# I2C_Switch.net
KiCad netlist of a schematic drawn in Altium Designer
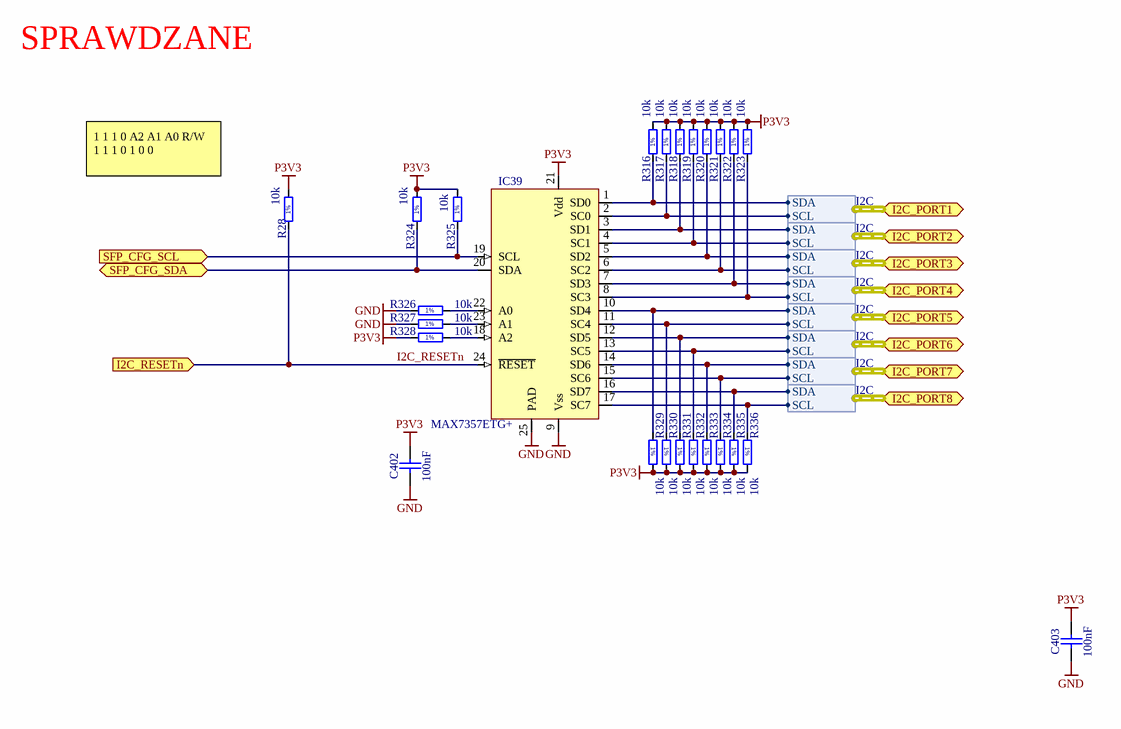
[diagram p0: I2C_Switch.SchDoc]

(export (version "E")
  (design (tool "Eeschema 10.0.6"))
  (components
    (comp (ref "C402")
      (value "100nF")
      (footprint "CAPC0603X33N")
      (description "Non-polarised capacitor")
      (fields
        (field (name "PART NUMBER") "CC0201_100NF_6.3V_10%_X5R")
        (field (name "VOLTAGE") "6.3V")
        (field (name "AUTHOR") "CERN DEM JLC")
      )
      (libsource (lib "Capacitors") (part "Capacitor - non polarized"))
    )
    (comp (ref "C403")
      (value "100nF")
      (footprint "CAPC0603X33N")
      (description "Non-polarised capacitor")
      (fields
        (field (name "PART NUMBER") "CC0201_100NF_6.3V_10%_X5R")
        (field (name "VOLTAGE") "6.3V")
        (field (name "AUTHOR") "CERN DEM JLC")
      )
      (libsource (lib "Capacitors") (part "Capacitor - non polarized"))
    )
    (comp (ref "IC39")
      (value "MAX7357ETG+")
      (footprint "QFN50P400X400X80-25N-S265")
      (description "8-channel I2C-bus multiplexer with reset, INT and timeout")
      (fields (field (name "MANUFACTURER") "MAXIM") (field (name "AUTHOR") "LNLS DIG GBMB"))
      (libsource (lib "ICs And Semiconductors") (part "MAX7357"))
    )
    (comp (ref "R28")
      (value "10k")
      (footprint "RESC1005X40N")
      (description "Resistor - 1%")
      (fields
        (field (name "PART NUMBER") "R0402_10K_1%_0.0625W_100PPM")
        (field (name "POWER") "0.0625W")
        (field (name "AUTHOR") "CERN DEM JLC")
      )
      (libsource (lib "Resistors") (part "Resistor - 1%"))
    )
    (comp (ref "R316")
      (value "10k")
      (footprint "RESC1005X40N")
      (description "Resistor - 1%")
      (fields
        (field (name "PART NUMBER") "R0402_10K_1%_0.0625W_100PPM")
        (field (name "POWER") "0.0625W")
        (field (name "AUTHOR") "CERN DEM JLC")
      )
      (libsource (lib "Resistors") (part "Resistor - 1%"))
    )
    (comp (ref "R317")
      (value "10k")
      (footprint "RESC1005X40N")
      (description "Resistor - 1%")
      (fields
        (field (name "PART NUMBER") "R0402_10K_1%_0.0625W_100PPM")
        (field (name "POWER") "0.0625W")
        (field (name "AUTHOR") "CERN DEM JLC")
      )
      (libsource (lib "Resistors") (part "Resistor - 1%"))
    )
    (comp (ref "R318")
      (value "10k")
      (footprint "RESC1005X40N")
      (description "Resistor - 1%")
      (fields
        (field (name "PART NUMBER") "R0402_10K_1%_0.0625W_100PPM")
        (field (name "POWER") "0.0625W")
        (field (name "AUTHOR") "CERN DEM JLC")
      )
      (libsource (lib "Resistors") (part "Resistor - 1%"))
    )
    (comp (ref "R319")
      (value "10k")
      (footprint "RESC1005X40N")
      (description "Resistor - 1%")
      (fields
        (field (name "PART NUMBER") "R0402_10K_1%_0.0625W_100PPM")
        (field (name "POWER") "0.0625W")
        (field (name "AUTHOR") "CERN DEM JLC")
      )
      (libsource (lib "Resistors") (part "Resistor - 1%"))
    )
    (comp (ref "R320")
      (value "10k")
      (footprint "RESC1005X40N")
      (description "Resistor - 1%")
      (fields
        (field (name "PART NUMBER") "R0402_10K_1%_0.0625W_100PPM")
        (field (name "POWER") "0.0625W")
        (field (name "AUTHOR") "CERN DEM JLC")
      )
      (libsource (lib "Resistors") (part "Resistor - 1%"))
    )
    (comp (ref "R321")
      (value "10k")
      (footprint "RESC1005X40N")
      (description "Resistor - 1%")
      (fields
        (field (name "PART NUMBER") "R0402_10K_1%_0.0625W_100PPM")
        (field (name "POWER") "0.0625W")
        (field (name "AUTHOR") "CERN DEM JLC")
      )
      (libsource (lib "Resistors") (part "Resistor - 1%"))
    )
    (comp (ref "R322")
      (value "10k")
      (footprint "RESC1005X40N")
      (description "Resistor - 1%")
      (fields
        (field (name "PART NUMBER") "R0402_10K_1%_0.0625W_100PPM")
        (field (name "POWER") "0.0625W")
        (field (name "AUTHOR") "CERN DEM JLC")
      )
      (libsource (lib "Resistors") (part "Resistor - 1%"))
    )
    (comp (ref "R323")
      (value "10k")
      (footprint "RESC1005X40N")
      (description "Resistor - 1%")
      (fields
        (field (name "PART NUMBER") "R0402_10K_1%_0.0625W_100PPM")
        (field (name "POWER") "0.0625W")
        (field (name "AUTHOR") "CERN DEM JLC")
      )
      (libsource (lib "Resistors") (part "Resistor - 1%"))
    )
    (comp (ref "R324")
      (value "10k")
      (footprint "RESC1005X40N")
      (description "Resistor - 1%")
      (fields
        (field (name "PART NUMBER") "R0402_10K_1%_0.0625W_100PPM")
        (field (name "POWER") "0.0625W")
        (field (name "AUTHOR") "CERN DEM JLC")
      )
      (libsource (lib "Resistors") (part "Resistor - 1%"))
    )
    (comp (ref "R325")
      (value "10k")
      (footprint "RESC1005X40N")
      (description "Resistor - 1%")
      (fields
        (field (name "PART NUMBER") "R0402_10K_1%_0.0625W_100PPM")
        (field (name "POWER") "0.0625W")
        (field (name "AUTHOR") "CERN DEM JLC")
      )
      (libsource (lib "Resistors") (part "Resistor - 1%"))
    )
    (comp (ref "R326")
      (value "10k")
      (footprint "RESC1005X40N")
      (description "Resistor - 1%")
      (fields
        (field (name "PART NUMBER") "R0402_10K_1%_0.0625W_100PPM")
        (field (name "POWER") "0.0625W")
        (field (name "AUTHOR") "CERN DEM JLC")
      )
      (libsource (lib "Resistors") (part "Resistor - 1%"))
    )
    (comp (ref "R327")
      (value "10k")
      (footprint "RESC1005X40N")
      (description "Resistor - 1%")
      (fields
        (field (name "PART NUMBER") "R0402_10K_1%_0.0625W_100PPM")
        (field (name "POWER") "0.0625W")
        (field (name "AUTHOR") "CERN DEM JLC")
      )
      (libsource (lib "Resistors") (part "Resistor - 1%"))
    )
    (comp (ref "R328")
      (value "10k")
      (footprint "RESC1005X40N")
      (description "Resistor - 1%")
      (fields
        (field (name "PART NUMBER") "R0402_10K_1%_0.0625W_100PPM")
        (field (name "POWER") "0.0625W")
        (field (name "AUTHOR") "CERN DEM JLC")
      )
      (libsource (lib "Resistors") (part "Resistor - 1%"))
    )
    (comp (ref "R329")
      (value "10k")
      (footprint "RESC1005X40N")
      (description "Resistor - 1%")
      (fields
        (field (name "PART NUMBER") "R0402_10K_1%_0.0625W_100PPM")
        (field (name "POWER") "0.0625W")
        (field (name "AUTHOR") "CERN DEM JLC")
      )
      (libsource (lib "Resistors") (part "Resistor - 1%"))
    )
    (comp (ref "R330")
      (value "10k")
      (footprint "RESC1005X40N")
      (description "Resistor - 1%")
      (fields
        (field (name "PART NUMBER") "R0402_10K_1%_0.0625W_100PPM")
        (field (name "POWER") "0.0625W")
        (field (name "AUTHOR") "CERN DEM JLC")
      )
      (libsource (lib "Resistors") (part "Resistor - 1%"))
    )
    (comp (ref "R331")
      (value "10k")
      (footprint "RESC1005X40N")
      (description "Resistor - 1%")
      (fields
        (field (name "PART NUMBER") "R0402_10K_1%_0.0625W_100PPM")
        (field (name "POWER") "0.0625W")
        (field (name "AUTHOR") "CERN DEM JLC")
      )
      (libsource (lib "Resistors") (part "Resistor - 1%"))
    )
    (comp (ref "R332")
      (value "10k")
      (footprint "RESC1005X40N")
      (description "Resistor - 1%")
      (fields
        (field (name "PART NUMBER") "R0402_10K_1%_0.0625W_100PPM")
        (field (name "POWER") "0.0625W")
        (field (name "AUTHOR") "CERN DEM JLC")
      )
      (libsource (lib "Resistors") (part "Resistor - 1%"))
    )
    (comp (ref "R333")
      (value "10k")
      (footprint "RESC1005X40N")
      (description "Resistor - 1%")
      (fields
        (field (name "PART NUMBER") "R0402_10K_1%_0.0625W_100PPM")
        (field (name "POWER") "0.0625W")
        (field (name "AUTHOR") "CERN DEM JLC")
      )
      (libsource (lib "Resistors") (part "Resistor - 1%"))
    )
    (comp (ref "R334")
      (value "10k")
      (footprint "RESC1005X40N")
      (description "Resistor - 1%")
      (fields
        (field (name "PART NUMBER") "R0402_10K_1%_0.0625W_100PPM")
        (field (name "POWER") "0.0625W")
        (field (name "AUTHOR") "CERN DEM JLC")
      )
      (libsource (lib "Resistors") (part "Resistor - 1%"))
    )
    (comp (ref "R335")
      (value "10k")
      (footprint "RESC1005X40N")
      (description "Resistor - 1%")
      (fields
        (field (name "PART NUMBER") "R0402_10K_1%_0.0625W_100PPM")
        (field (name "POWER") "0.0625W")
        (field (name "AUTHOR") "CERN DEM JLC")
      )
      (libsource (lib "Resistors") (part "Resistor - 1%"))
    )
    (comp (ref "R336")
      (value "10k")
      (footprint "RESC1005X40N")
      (description "Resistor - 1%")
      (fields
        (field (name "PART NUMBER") "R0402_10K_1%_0.0625W_100PPM")
        (field (name "POWER") "0.0625W")
        (field (name "AUTHOR") "CERN DEM JLC")
      )
      (libsource (lib "Resistors") (part "Resistor - 1%"))
    )
  )
  (nets
    (net (code "4") (name "/I2C_RESETn") (class "Default")
      (node (ref "IC39") (pin "24") (pinfunction "~{RESET}_24") (pintype "input"))
      (node (ref "R28") (pin "1") (pinfunction "1_1") (pintype "passive"))
    )
    (net (code "5") (name "/SFP_CFG_SCL") (class "Default")
      (node (ref "IC39") (pin "19") (pinfunction "SCL_19") (pintype "input"))
      (node (ref "R325") (pin "1") (pinfunction "1_1") (pintype "passive"))
    )
    (net (code "6") (name "/SFP_CFG_SDA") (class "Default")
      (node (ref "IC39") (pin "20") (pinfunction "SDA_20") (pintype "bidirectional"))
      (node (ref "R324") (pin "1") (pinfunction "1_1") (pintype "passive"))
    )
    (net (code "8") (name "GND") (class "Default")
      (node (ref "C402") (pin "1") (pinfunction "1_1") (pintype "passive"))
      (node (ref "C403") (pin "1") (pinfunction "1_1") (pintype "passive"))
      (node (ref "IC39") (pin "25") (pinfunction "PAD_25") (pintype "power_in"))
      (node (ref "IC39") (pin "9") (pinfunction "Vss_9") (pintype "power_in"))
      (node (ref "R326") (pin "1") (pinfunction "1_1") (pintype "passive"))
      (node (ref "R327") (pin "1") (pinfunction "1_1") (pintype "passive"))
    )
    (net (code "9") (name "Net-(IC39-A0)") (class "Default")
      (node (ref "IC39") (pin "22") (pinfunction "A0_22") (pintype "input"))
      (node (ref "R326") (pin "2") (pinfunction "2_2") (pintype "passive"))
    )
    (net (code "10") (name "Net-(IC39-A1)") (class "Default")
      (node (ref "IC39") (pin "23") (pinfunction "A1_23") (pintype "input"))
      (node (ref "R327") (pin "2") (pinfunction "2_2") (pintype "passive"))
    )
    (net (code "11") (name "Net-(IC39-A2)") (class "Default")
      (node (ref "IC39") (pin "18") (pinfunction "A2_18") (pintype "input"))
      (node (ref "R328") (pin "2") (pinfunction "2_2") (pintype "passive"))
    )
    (net (code "12") (name "Net-(IC39-SC0)") (class "Default")
      (node (ref "IC39") (pin "2") (pinfunction "SC0_2") (pintype "bidirectional"))
      (node (ref "R317") (pin "1") (pinfunction "1_1") (pintype "passive"))
    )
    (net (code "13") (name "Net-(IC39-SC1)") (class "Default")
      (node (ref "IC39") (pin "4") (pinfunction "SC1_4") (pintype "bidirectional"))
      (node (ref "R319") (pin "1") (pinfunction "1_1") (pintype "passive"))
    )
    (net (code "14") (name "Net-(IC39-SC2)") (class "Default")
      (node (ref "IC39") (pin "6") (pinfunction "SC2_6") (pintype "bidirectional"))
      (node (ref "R321") (pin "1") (pinfunction "1_1") (pintype "passive"))
    )
    (net (code "15") (name "Net-(IC39-SC3)") (class "Default")
      (node (ref "IC39") (pin "8") (pinfunction "SC3_8") (pintype "bidirectional"))
      (node (ref "R323") (pin "1") (pinfunction "1_1") (pintype "passive"))
    )
    (net (code "16") (name "Net-(IC39-SC4)") (class "Default")
      (node (ref "IC39") (pin "11") (pinfunction "SC4_11") (pintype "bidirectional"))
      (node (ref "R330") (pin "1") (pinfunction "1_1") (pintype "passive"))
    )
    (net (code "17") (name "Net-(IC39-SC5)") (class "Default")
      (node (ref "IC39") (pin "13") (pinfunction "SC5_13") (pintype "bidirectional"))
      (node (ref "R332") (pin "1") (pinfunction "1_1") (pintype "passive"))
    )
    (net (code "18") (name "Net-(IC39-SC6)") (class "Default")
      (node (ref "IC39") (pin "15") (pinfunction "SC6_15") (pintype "bidirectional"))
      (node (ref "R334") (pin "1") (pinfunction "1_1") (pintype "passive"))
    )
    (net (code "19") (name "Net-(IC39-SC7)") (class "Default")
      (node (ref "IC39") (pin "17") (pinfunction "SC7_17") (pintype "bidirectional"))
      (node (ref "R336") (pin "1") (pinfunction "1_1") (pintype "passive"))
    )
    (net (code "20") (name "Net-(IC39-SD0)") (class "Default")
      (node (ref "IC39") (pin "1") (pinfunction "SD0_1") (pintype "bidirectional"))
      (node (ref "R316") (pin "1") (pinfunction "1_1") (pintype "passive"))
    )
    (net (code "21") (name "Net-(IC39-SD1)") (class "Default")
      (node (ref "IC39") (pin "3") (pinfunction "SD1_3") (pintype "bidirectional"))
      (node (ref "R318") (pin "1") (pinfunction "1_1") (pintype "passive"))
    )
    (net (code "22") (name "Net-(IC39-SD2)") (class "Default")
      (node (ref "IC39") (pin "5") (pinfunction "SD2_5") (pintype "bidirectional"))
      (node (ref "R320") (pin "1") (pinfunction "1_1") (pintype "passive"))
    )
    (net (code "23") (name "Net-(IC39-SD3)") (class "Default")
      (node (ref "IC39") (pin "7") (pinfunction "SD3_7") (pintype "bidirectional"))
      (node (ref "R322") (pin "1") (pinfunction "1_1") (pintype "passive"))
    )
    (net (code "24") (name "Net-(IC39-SD4)") (class "Default")
      (node (ref "IC39") (pin "10") (pinfunction "SD4_10") (pintype "bidirectional"))
      (node (ref "R329") (pin "1") (pinfunction "1_1") (pintype "passive"))
    )
    (net (code "25") (name "Net-(IC39-SD5)") (class "Default")
      (node (ref "IC39") (pin "12") (pinfunction "SD5_12") (pintype "bidirectional"))
      (node (ref "R331") (pin "1") (pinfunction "1_1") (pintype "passive"))
    )
    (net (code "26") (name "Net-(IC39-SD6)") (class "Default")
      (node (ref "IC39") (pin "14") (pinfunction "SD6_14") (pintype "bidirectional"))
      (node (ref "R333") (pin "1") (pinfunction "1_1") (pintype "passive"))
    )
    (net (code "27") (name "Net-(IC39-SD7)") (class "Default")
      (node (ref "IC39") (pin "16") (pinfunction "SD7_16") (pintype "bidirectional"))
      (node (ref "R335") (pin "1") (pinfunction "1_1") (pintype "passive"))
    )
    (net (code "28") (name "P3V3") (class "Default")
      (node (ref "C402") (pin "2") (pinfunction "2_2") (pintype "passive"))
      (node (ref "C403") (pin "2") (pinfunction "2_2") (pintype "passive"))
      (node (ref "IC39") (pin "21") (pinfunction "Vdd_21") (pintype "power_in"))
      (node (ref "R28") (pin "2") (pinfunction "2_2") (pintype "passive"))
      (node (ref "R316") (pin "2") (pinfunction "2_2") (pintype "passive"))
      (node (ref "R317") (pin "2") (pinfunction "2_2") (pintype "passive"))
      (node (ref "R318") (pin "2") (pinfunction "2_2") (pintype "passive"))
      (node (ref "R319") (pin "2") (pinfunction "2_2") (pintype "passive"))
      (node (ref "R320") (pin "2") (pinfunction "2_2") (pintype "passive"))
      (node (ref "R321") (pin "2") (pinfunction "2_2") (pintype "passive"))
      (node (ref "R322") (pin "2") (pinfunction "2_2") (pintype "passive"))
      (node (ref "R323") (pin "2") (pinfunction "2_2") (pintype "passive"))
      (node (ref "R324") (pin "2") (pinfunction "2_2") (pintype "passive"))
      (node (ref "R325") (pin "2") (pinfunction "2_2") (pintype "passive"))
      (node (ref "R328") (pin "1") (pinfunction "1_1") (pintype "passive"))
      (node (ref "R329") (pin "2") (pinfunction "2_2") (pintype "passive"))
      (node (ref "R330") (pin "2") (pinfunction "2_2") (pintype "passive"))
      (node (ref "R331") (pin "2") (pinfunction "2_2") (pintype "passive"))
      (node (ref "R332") (pin "2") (pinfunction "2_2") (pintype "passive"))
      (node (ref "R333") (pin "2") (pinfunction "2_2") (pintype "passive"))
      (node (ref "R334") (pin "2") (pinfunction "2_2") (pintype "passive"))
      (node (ref "R335") (pin "2") (pinfunction "2_2") (pintype "passive"))
      (node (ref "R336") (pin "2") (pinfunction "2_2") (pintype "passive"))
    )
  )
)
